# 11_PHY_FE_17-24.net
KiCad netlist of a schematic drawn in Altium Designer
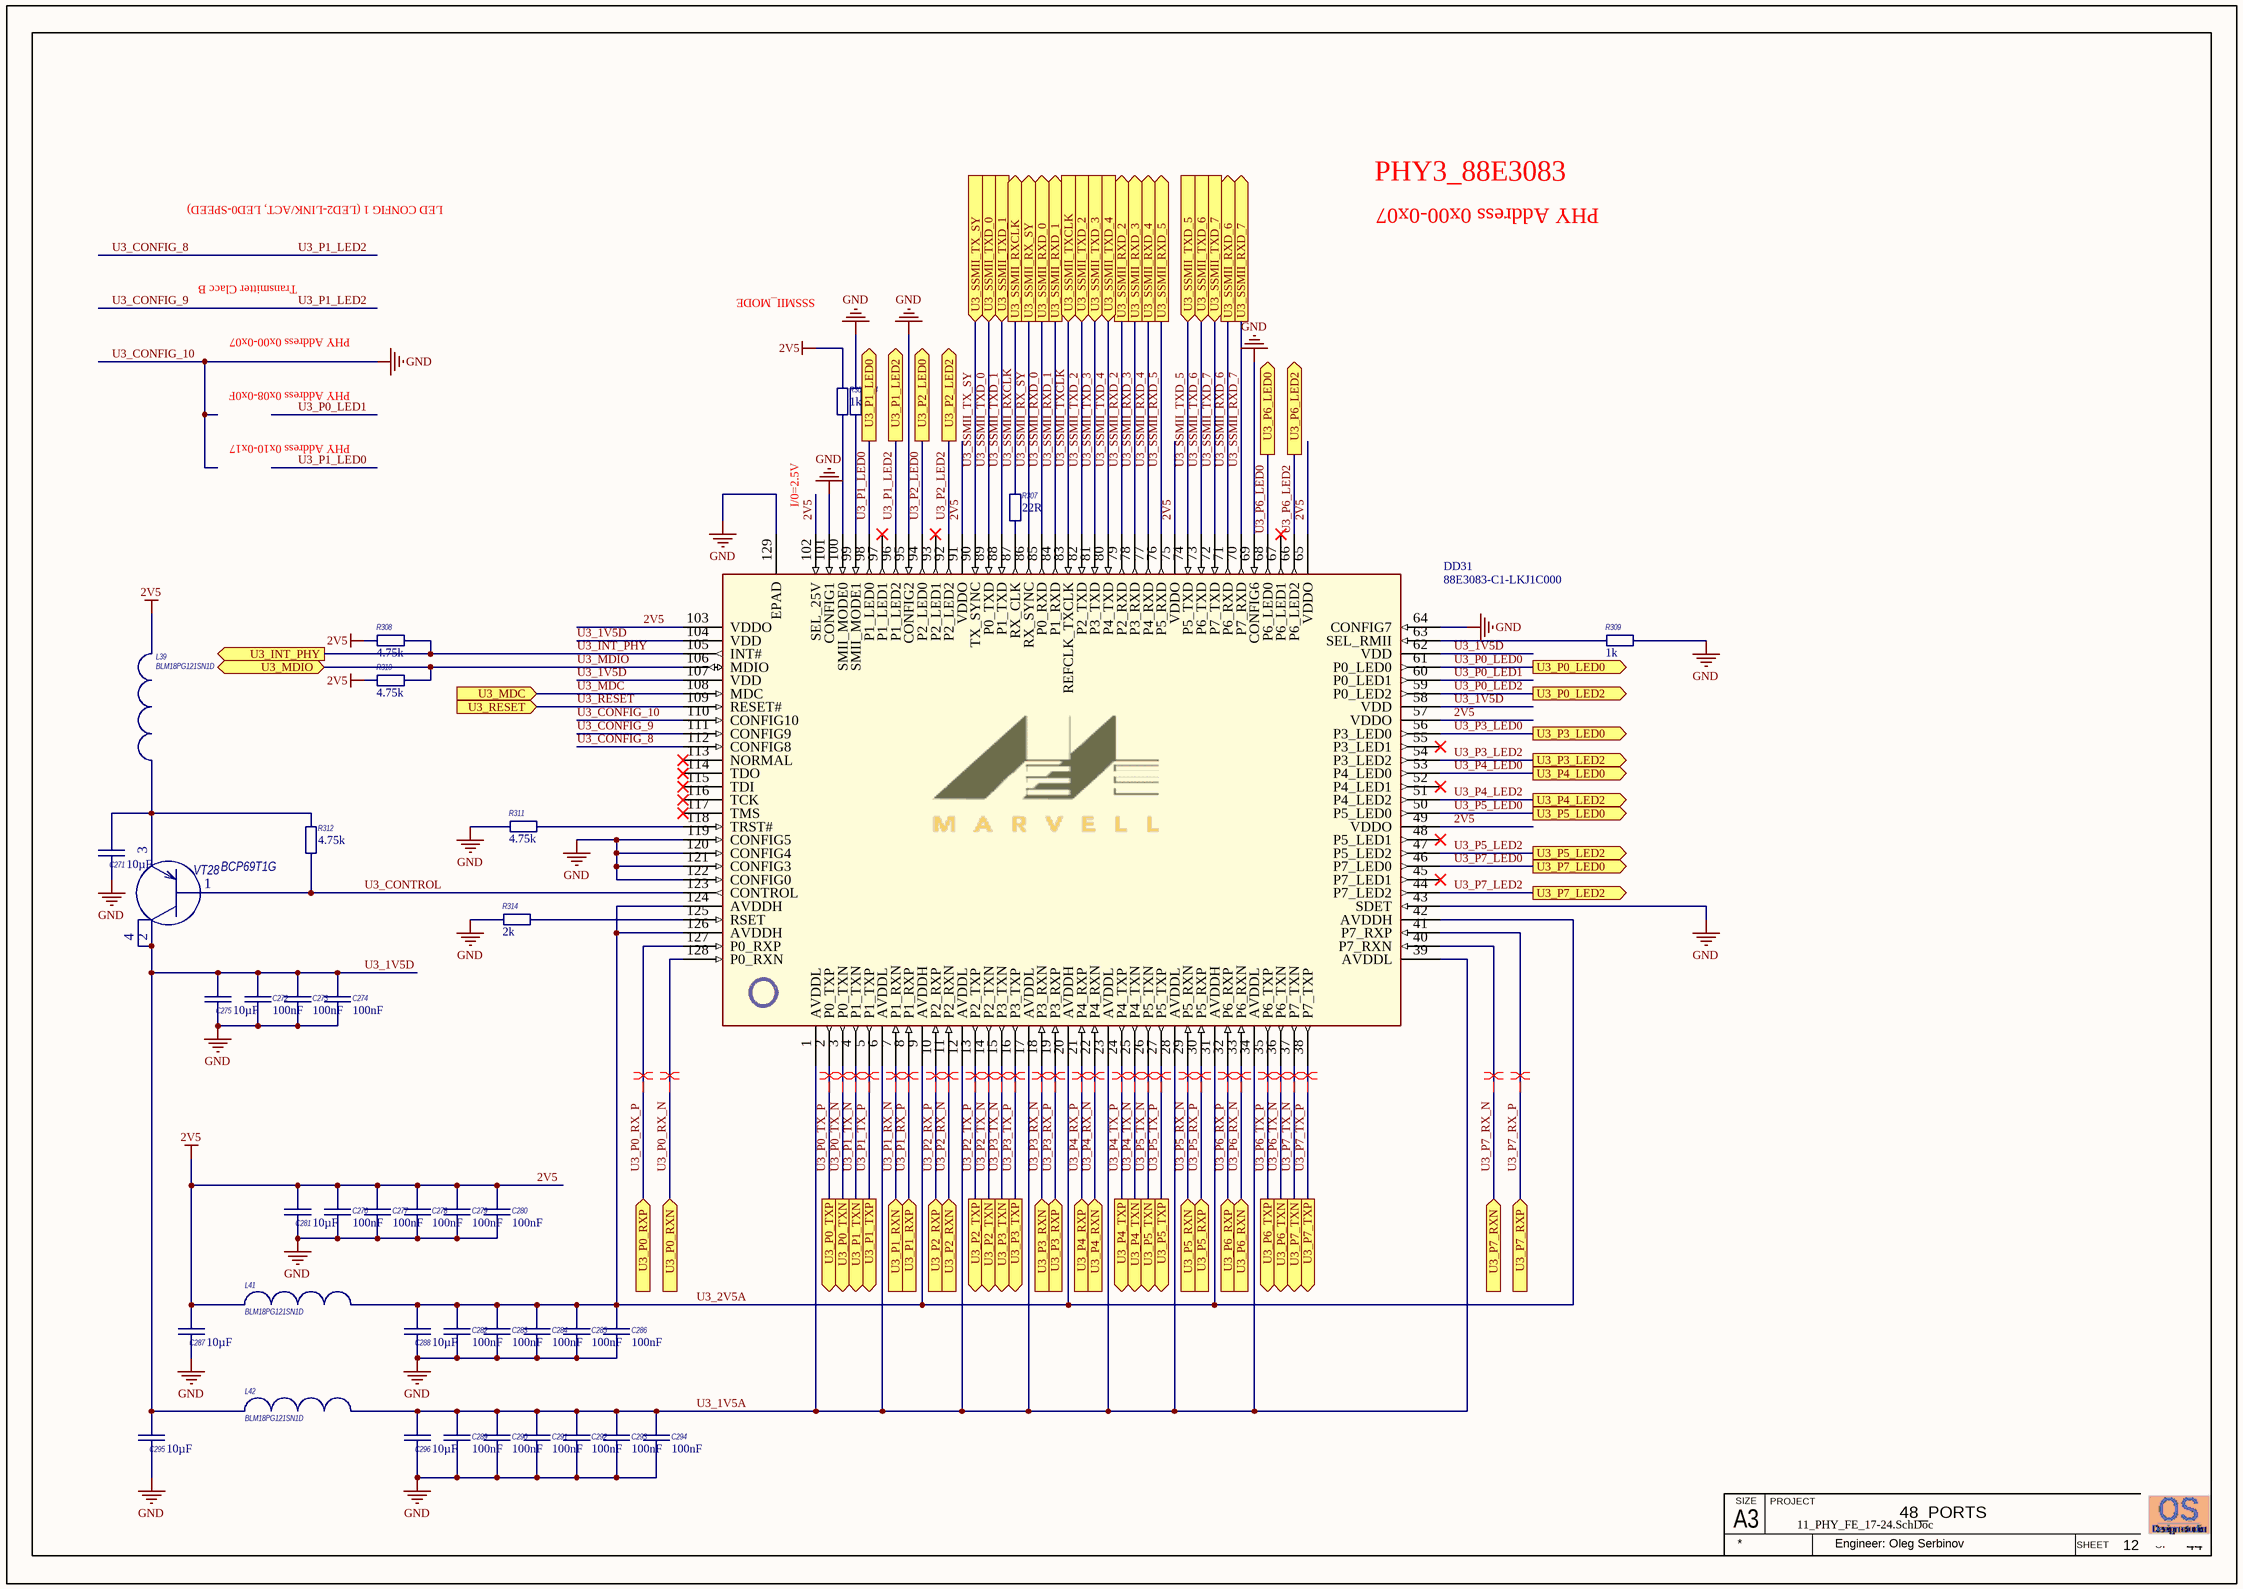
[diagram p0: 11_PHY_FE_17-24.SchDoc]

(export (version "E")
  (design (tool "Eeschema 10.0.6"))
  (components
    (comp (ref "C271")
      (value "GRM21BR61C106KE15")
      (footprint "CAPC2012[0805]")
      (description "C0805, 10uF 10%, 16V, X5R")
      (fields
        (field (name "MANUFACTURER") "Murata")
        (field (name "TOLERANCE") "±10%")
        (field (name "CAPACITANCE") "10µF")
      )
      (libsource (lib "CAPACITORS") (part "GRM21BR61C106KE15"))
    )
    (comp (ref "C272")
      (value "GRM155R71E104KE14D")
      (footprint "C0402_IPC High Density")
      (description "C0402, 100nF, 25V, X7R")
      (fields
        (field (name "MANUFACTURER") "Murata")
        (field (name "CAPACITANCE") "100nF")
        (field (name "CUSTOMER PART NUMBER") "Конденсатор, 100n, 0402, 25V, X7R, 10%")
      )
      (libsource (lib "CAPACITORS") (part "GRM155R71E104KE14D"))
    )
    (comp (ref "C273")
      (value "GRM155R71E104KE14D")
      (footprint "C0402_IPC High Density")
      (description "C0402, 100nF, 25V, X7R")
      (fields
        (field (name "MANUFACTURER") "Murata")
        (field (name "CAPACITANCE") "100nF")
        (field (name "CUSTOMER PART NUMBER") "Конденсатор, 100n, 0402, 25V, X7R, 10%")
      )
      (libsource (lib "CAPACITORS") (part "GRM155R71E104KE14D"))
    )
    (comp (ref "C274")
      (value "GRM155R71E104KE14D")
      (footprint "C0402_IPC High Density")
      (description "C0402, 100nF, 25V, X7R")
      (fields
        (field (name "MANUFACTURER") "Murata")
        (field (name "CAPACITANCE") "100nF")
        (field (name "CUSTOMER PART NUMBER") "Конденсатор, 100n, 0402, 25V, X7R, 10%")
      )
      (libsource (lib "CAPACITORS") (part "GRM155R71E104KE14D"))
    )
    (comp (ref "C275")
      (value "GRM21BR61C106KE15")
      (footprint "CAPC2012[0805]")
      (description "C0805, 10uF 10%, 16V, X5R")
      (fields
        (field (name "MANUFACTURER") "Murata")
        (field (name "TOLERANCE") "±10%")
        (field (name "CAPACITANCE") "10µF")
      )
      (libsource (lib "CAPACITORS") (part "GRM21BR61C106KE15"))
    )
    (comp (ref "C276")
      (value "GRM155R71E104KE14D")
      (footprint "C0402_IPC High Density")
      (description "C0402, 100nF, 25V, X7R")
      (fields
        (field (name "MANUFACTURER") "Murata")
        (field (name "CAPACITANCE") "100nF")
        (field (name "CUSTOMER PART NUMBER") "Конденсатор, 100n, 0402, 25V, X7R, 10%")
      )
      (libsource (lib "CAPACITORS") (part "GRM155R71E104KE14D"))
    )
    (comp (ref "C277")
      (value "GRM155R71E104KE14D")
      (footprint "C0402_IPC High Density")
      (description "C0402, 100nF, 25V, X7R")
      (fields
        (field (name "MANUFACTURER") "Murata")
        (field (name "CAPACITANCE") "100nF")
        (field (name "CUSTOMER PART NUMBER") "Конденсатор, 100n, 0402, 25V, X7R, 10%")
      )
      (libsource (lib "CAPACITORS") (part "GRM155R71E104KE14D"))
    )
    (comp (ref "C278")
      (value "GRM155R71E104KE14D")
      (footprint "C0402_IPC High Density")
      (description "C0402, 100nF, 25V, X7R")
      (fields
        (field (name "MANUFACTURER") "Murata")
        (field (name "CAPACITANCE") "100nF")
        (field (name "CUSTOMER PART NUMBER") "Конденсатор, 100n, 0402, 25V, X7R, 10%")
      )
      (libsource (lib "CAPACITORS") (part "GRM155R71E104KE14D"))
    )
    (comp (ref "C279")
      (value "GRM155R71E104KE14D")
      (footprint "C0402_IPC High Density")
      (description "C0402, 100nF, 25V, X7R")
      (fields
        (field (name "MANUFACTURER") "Murata")
        (field (name "CAPACITANCE") "100nF")
        (field (name "CUSTOMER PART NUMBER") "Конденсатор, 100n, 0402, 25V, X7R, 10%")
      )
      (libsource (lib "CAPACITORS") (part "GRM155R71E104KE14D"))
    )
    (comp (ref "C280")
      (value "GRM155R71E104KE14D")
      (footprint "C0402_IPC High Density")
      (description "C0402, 100nF, 25V, X7R")
      (fields
        (field (name "MANUFACTURER") "Murata")
        (field (name "CAPACITANCE") "100nF")
        (field (name "CUSTOMER PART NUMBER") "Конденсатор, 100n, 0402, 25V, X7R, 10%")
      )
      (libsource (lib "CAPACITORS") (part "GRM155R71E104KE14D"))
    )
    (comp (ref "C281")
      (value "GRM21BR61C106KE15")
      (footprint "CAPC2012[0805]")
      (description "C0805, 10uF 10%, 16V, X5R")
      (fields
        (field (name "MANUFACTURER") "Murata")
        (field (name "TOLERANCE") "±10%")
        (field (name "CAPACITANCE") "10µF")
      )
      (libsource (lib "CAPACITORS") (part "GRM21BR61C106KE15"))
    )
    (comp (ref "C282")
      (value "GRM155R71E104KE14D")
      (footprint "C0402_IPC High Density")
      (description "C0402, 100nF, 25V, X7R")
      (fields
        (field (name "MANUFACTURER") "Murata")
        (field (name "CAPACITANCE") "100nF")
        (field (name "CUSTOMER PART NUMBER") "Конденсатор, 100n, 0402, 25V, X7R, 10%")
      )
      (libsource (lib "CAPACITORS") (part "GRM155R71E104KE14D"))
    )
    (comp (ref "C283")
      (value "GRM155R71E104KE14D")
      (footprint "C0402_IPC High Density")
      (description "C0402, 100nF, 25V, X7R")
      (fields
        (field (name "MANUFACTURER") "Murata")
        (field (name "CAPACITANCE") "100nF")
        (field (name "CUSTOMER PART NUMBER") "Конденсатор, 100n, 0402, 25V, X7R, 10%")
      )
      (libsource (lib "CAPACITORS") (part "GRM155R71E104KE14D"))
    )
    (comp (ref "C284")
      (value "GRM155R71E104KE14D")
      (footprint "C0402_IPC High Density")
      (description "C0402, 100nF, 25V, X7R")
      (fields
        (field (name "MANUFACTURER") "Murata")
        (field (name "CAPACITANCE") "100nF")
        (field (name "CUSTOMER PART NUMBER") "Конденсатор, 100n, 0402, 25V, X7R, 10%")
      )
      (libsource (lib "CAPACITORS") (part "GRM155R71E104KE14D"))
    )
    (comp (ref "C285")
      (value "GRM155R71E104KE14D")
      (footprint "C0402_IPC High Density")
      (description "C0402, 100nF, 25V, X7R")
      (fields
        (field (name "MANUFACTURER") "Murata")
        (field (name "CAPACITANCE") "100nF")
        (field (name "CUSTOMER PART NUMBER") "Конденсатор, 100n, 0402, 25V, X7R, 10%")
      )
      (libsource (lib "CAPACITORS") (part "GRM155R71E104KE14D"))
    )
    (comp (ref "C286")
      (value "GRM155R71E104KE14D")
      (footprint "C0402_IPC High Density")
      (description "C0402, 100nF, 25V, X7R")
      (fields
        (field (name "MANUFACTURER") "Murata")
        (field (name "CAPACITANCE") "100nF")
        (field (name "CUSTOMER PART NUMBER") "Конденсатор, 100n, 0402, 25V, X7R, 10%")
      )
      (libsource (lib "CAPACITORS") (part "GRM155R71E104KE14D"))
    )
    (comp (ref "C287")
      (value "GRM21BR61C106KE15")
      (footprint "CAPC2012[0805]")
      (description "C0805, 10uF 10%, 16V, X5R")
      (fields
        (field (name "MANUFACTURER") "Murata")
        (field (name "TOLERANCE") "±10%")
        (field (name "CAPACITANCE") "10µF")
      )
      (libsource (lib "CAPACITORS") (part "GRM21BR61C106KE15"))
    )
    (comp (ref "C288")
      (value "GRM21BR61C106KE15")
      (footprint "CAPC2012[0805]")
      (description "C0805, 10uF 10%, 16V, X5R")
      (fields
        (field (name "MANUFACTURER") "Murata")
        (field (name "TOLERANCE") "±10%")
        (field (name "CAPACITANCE") "10µF")
      )
      (libsource (lib "CAPACITORS") (part "GRM21BR61C106KE15"))
    )
    (comp (ref "C289")
      (value "GRM155R71E104KE14D")
      (footprint "C0402_IPC High Density")
      (description "C0402, 100nF, 25V, X7R")
      (fields
        (field (name "MANUFACTURER") "Murata")
        (field (name "CAPACITANCE") "100nF")
        (field (name "CUSTOMER PART NUMBER") "Конденсатор, 100n, 0402, 25V, X7R, 10%")
      )
      (libsource (lib "CAPACITORS") (part "GRM155R71E104KE14D"))
    )
    (comp (ref "C290")
      (value "GRM155R71E104KE14D")
      (footprint "C0402_IPC High Density")
      (description "C0402, 100nF, 25V, X7R")
      (fields
        (field (name "MANUFACTURER") "Murata")
        (field (name "CAPACITANCE") "100nF")
        (field (name "CUSTOMER PART NUMBER") "Конденсатор, 100n, 0402, 25V, X7R, 10%")
      )
      (libsource (lib "CAPACITORS") (part "GRM155R71E104KE14D"))
    )
    (comp (ref "C291")
      (value "GRM155R71E104KE14D")
      (footprint "C0402_IPC High Density")
      (description "C0402, 100nF, 25V, X7R")
      (fields
        (field (name "MANUFACTURER") "Murata")
        (field (name "CAPACITANCE") "100nF")
        (field (name "CUSTOMER PART NUMBER") "Конденсатор, 100n, 0402, 25V, X7R, 10%")
      )
      (libsource (lib "CAPACITORS") (part "GRM155R71E104KE14D"))
    )
    (comp (ref "C292")
      (value "GRM155R71E104KE14D")
      (footprint "C0402_IPC High Density")
      (description "C0402, 100nF, 25V, X7R")
      (fields
        (field (name "MANUFACTURER") "Murata")
        (field (name "CAPACITANCE") "100nF")
        (field (name "CUSTOMER PART NUMBER") "Конденсатор, 100n, 0402, 25V, X7R, 10%")
      )
      (libsource (lib "CAPACITORS") (part "GRM155R71E104KE14D"))
    )
    (comp (ref "C293")
      (value "GRM155R71E104KE14D")
      (footprint "C0402_IPC High Density")
      (description "C0402, 100nF, 25V, X7R")
      (fields
        (field (name "MANUFACTURER") "Murata")
        (field (name "CAPACITANCE") "100nF")
        (field (name "CUSTOMER PART NUMBER") "Конденсатор, 100n, 0402, 25V, X7R, 10%")
      )
      (libsource (lib "CAPACITORS") (part "GRM155R71E104KE14D"))
    )
    (comp (ref "C294")
      (value "GRM155R71E104KE14D")
      (footprint "C0402_IPC High Density")
      (description "C0402, 100nF, 25V, X7R")
      (fields
        (field (name "MANUFACTURER") "Murata")
        (field (name "CAPACITANCE") "100nF")
        (field (name "CUSTOMER PART NUMBER") "Конденсатор, 100n, 0402, 25V, X7R, 10%")
      )
      (libsource (lib "CAPACITORS") (part "GRM155R71E104KE14D"))
    )
    (comp (ref "C295")
      (value "GRM21BR61C106KE15")
      (footprint "CAPC2012[0805]")
      (description "C0805, 10uF 10%, 16V, X5R")
      (fields
        (field (name "MANUFACTURER") "Murata")
        (field (name "TOLERANCE") "±10%")
        (field (name "CAPACITANCE") "10µF")
      )
      (libsource (lib "CAPACITORS") (part "GRM21BR61C106KE15"))
    )
    (comp (ref "C296")
      (value "GRM21BR61C106KE15")
      (footprint "CAPC2012[0805]")
      (description "C0805, 10uF 10%, 16V, X5R")
      (fields
        (field (name "MANUFACTURER") "Murata")
        (field (name "TOLERANCE") "±10%")
        (field (name "CAPACITANCE") "10µF")
      )
      (libsource (lib "CAPACITORS") (part "GRM21BR61C106KE15"))
    )
    (comp (ref "DD31")
      (value "88E3083-C1-LKJ1C000")
      (footprint "LQFP-128N")
      (description "IC 10/100BASE-T OCTAL PHY")
      (fields
        (field (name "CUSTOMER PART NUMBER") "Микросхема, 88E3083-C1-LKJ1C000, IC 10/100BASE-T OCTAL PHY, 128 LQFP")
        (field (name "MANUFACTURER") "Marvell Technology Group")
      )
      (libsource (lib "DIGITAL and ANALIG ICs") (part "88E3083-C1-LKJ1C000"))
    )
    (comp (ref "L39")
      (value "BLM18PG121SN1D")
      (footprint "INDC1608X95N")
      (description "FILTER BLM18 (0603, 2A)")
      (fields
        (field (name "MANUFACTURER") "Murata")
        (field (name "RPART NUMBER") "MPZ1608S121ATAH0 ; CIC10P121NC ; MPZ1608S121ATDH5 ; BLM18PG121SH1D ; 742792625")
      )
      (libsource (lib "INDUCTORS") (part "BLM18PG121SN1D"))
    )
    (comp (ref "L41")
      (value "BLM18PG121SN1D")
      (footprint "INDC1608X95N")
      (description "FILTER BLM18 (0603, 2A)")
      (fields
        (field (name "MANUFACTURER") "Murata")
        (field (name "RPART NUMBER") "MPZ1608S121ATAH0 ; CIC10P121NC ; MPZ1608S121ATDH5 ; BLM18PG121SH1D ; 742792625")
      )
      (libsource (lib "INDUCTORS") (part "BLM18PG121SN1D"))
    )
    (comp (ref "L42")
      (value "BLM18PG121SN1D")
      (footprint "INDC1608X95N")
      (description "FILTER BLM18 (0603, 2A)")
      (fields
        (field (name "MANUFACTURER") "Murata")
        (field (name "RPART NUMBER") "MPZ1608S121ATAH0 ; CIC10P121NC ; MPZ1608S121ATDH5 ; BLM18PG121SH1D ; 742792625")
      )
      (libsource (lib "INDUCTORS") (part "BLM18PG121SN1D"))
    )
    (comp (ref "R303")
      (value "ERJ-2RKF1001X")
      (footprint "R0402_IPC High Density")
      (description "R0402, 1k 1%")
      (fields
        (field (name "MANUFACTURER") "Panasonic")
        (field (name "TOLERANCE") "1 %")
        (field (name "RESISTANCE") "1k")
      )
      (libsource (lib "RESISTOR") (part "ERJ-2RKF1001X"))
    )
    (comp (ref "R304")
      (value "ERJ-2RKF1001X")
      (footprint "R0402_IPC High Density")
      (description "R0402, 1k 1%")
      (fields
        (field (name "MANUFACTURER") "Panasonic")
        (field (name "TOLERANCE") "1 %")
        (field (name "RESISTANCE") "1k")
      )
      (libsource (lib "RESISTOR") (part "ERJ-2RKF1001X"))
    )
    (comp (ref "R307")
      (value "ERJ-2RKF22R0X")
      (footprint "R0402_IPC High Density")
      (description "R0402, 22R 1%")
      (fields
        (field (name "MANUFACTURER") "Panasonic")
        (field (name "RESISTANCE") "22R")
        (field (name "CUSTOMER PART NUMBER") "Резистор, 22R, 0402, 1%")
      )
      (libsource (lib "RESISTOR") (part "ERJ-2RKF22R0X"))
    )
    (comp (ref "R308")
      (value "ERJ-2RKF4751X")
      (footprint "R0402_IPC High Density")
      (description "R0402, 4.75k 1%")
      (fields
        (field (name "TOLERANCE") "±1%")
        (field (name "MANUFACTURER") "Panasonic")
        (field (name "RESISTANCE (OHMS)") "4.75k")
      )
      (libsource (lib "RESISTOR") (part "ERJ-2RKF4751X"))
    )
    (comp (ref "R309")
      (value "ERJ-2RKF1001X")
      (footprint "R0402_IPC High Density")
      (description "R0402, 1k 1%")
      (fields
        (field (name "MANUFACTURER") "Panasonic")
        (field (name "TOLERANCE") "1 %")
        (field (name "RESISTANCE") "1k")
      )
      (libsource (lib "RESISTOR") (part "ERJ-2RKF1001X"))
    )
    (comp (ref "R310")
      (value "ERJ-2RKF4751X")
      (footprint "R0402_IPC High Density")
      (description "R0402, 4.75k 1%")
      (fields
        (field (name "TOLERANCE") "±1%")
        (field (name "MANUFACTURER") "Panasonic")
        (field (name "RESISTANCE (OHMS)") "4.75k")
      )
      (libsource (lib "RESISTOR") (part "ERJ-2RKF4751X"))
    )
    (comp (ref "R311")
      (value "ERJ-2RKF4751X")
      (footprint "R0402_IPC High Density")
      (description "R0402, 4.75k 1%")
      (fields
        (field (name "TOLERANCE") "±1%")
        (field (name "MANUFACTURER") "Panasonic")
        (field (name "RESISTANCE (OHMS)") "4.75k")
      )
      (libsource (lib "RESISTOR") (part "ERJ-2RKF4751X"))
    )
    (comp (ref "R312")
      (value "ERJ-2RKF4751X")
      (footprint "R0402_IPC High Density")
      (description "R0402, 4.75k 1%")
      (fields
        (field (name "TOLERANCE") "±1%")
        (field (name "MANUFACTURER") "Panasonic")
        (field (name "RESISTANCE (OHMS)") "4.75k")
      )
      (libsource (lib "RESISTOR") (part "ERJ-2RKF4751X"))
    )
    (comp (ref "R314")
      (value "ERJ-2RKF2001X")
      (footprint "R0402_IPC High Density")
      (description "R0402, 2k 1%")
      (fields
        (field (name "TOLERANCE") "±1%")
        (field (name "MANUFACTURER") "Panasonic")
        (field (name "RESISTANCE (OHMS)") "2k")
      )
      (libsource (lib "RESISTOR") (part "ERJ-2RKF2001X"))
    )
    (comp (ref "VT28")
      (value "BCP69T1G")
      (footprint "SOT223_N")
      (description "TRANSISTOR PNP -20V -1A SOT-223")
      (fields
        (field (name "MANUFACTURER") "ON Semiconductor")
        (field (name "MANUFACTURER PART NUMBER") "BCP69T1")
      )
      (libsource (lib "TRANSISTORS") (part "BCP69T1"))
    )
  )
  (nets
    (net (code "1") (name "/U3_1V5A") (class "Default")
      (node (ref "C289") (pin "2") (pintype "passive"))
      (node (ref "C290") (pin "2") (pintype "passive"))
      (node (ref "C291") (pin "2") (pintype "passive"))
      (node (ref "C292") (pin "2") (pintype "passive"))
      (node (ref "C293") (pin "2") (pintype "passive"))
      (node (ref "C294") (pin "2") (pintype "passive"))
      (node (ref "C296") (pin "2") (pintype "passive"))
      (node (ref "DD31") (pin "1") (pinfunction "AVDDL_1") (pintype "power_in"))
      (node (ref "DD31") (pin "12") (pinfunction "AVDDL_12") (pintype "power_in"))
      (node (ref "DD31") (pin "17") (pinfunction "AVDDL_17") (pintype "power_in"))
      (node (ref "DD31") (pin "23") (pinfunction "AVDDL_23") (pintype "power_in"))
      (node (ref "DD31") (pin "28") (pinfunction "AVDDL_28") (pintype "power_in"))
      (node (ref "DD31") (pin "34") (pinfunction "AVDDL_34") (pintype "power_in"))
      (node (ref "DD31") (pin "39") (pinfunction "AVDDL_39") (pintype "power_in"))
      (node (ref "DD31") (pin "6") (pinfunction "AVDDL_6") (pintype "power_in"))
      (node (ref "L42") (pin "2") (pinfunction "2_2") (pintype "passive"))
    )
    (net (code "2") (name "/U3_1V5D") (class "Default")
      (node (ref "C272") (pin "2") (pintype "passive"))
      (node (ref "C273") (pin "2") (pintype "passive"))
      (node (ref "C274") (pin "2") (pintype "passive"))
      (node (ref "C275") (pin "2") (pintype "passive"))
      (node (ref "C295") (pin "2") (pintype "passive"))
      (node (ref "DD31") (pin "104") (pinfunction "VDD_104") (pintype "power_in"))
      (node (ref "DD31") (pin "107") (pinfunction "VDD_107") (pintype "power_in"))
      (node (ref "DD31") (pin "58") (pinfunction "VDD_58") (pintype "power_in"))
      (node (ref "DD31") (pin "62") (pinfunction "VDD_62") (pintype "power_in"))
      (node (ref "L42") (pin "1") (pinfunction "1_1") (pintype "passive"))
      (node (ref "VT28") (pin "2") (pinfunction "K_2") (pintype "passive"))
      (node (ref "VT28") (pin "4") (pinfunction "K_4") (pintype "passive"))
    )
    (net (code "3") (name "/U3_2V5A") (class "Default")
      (node (ref "C282") (pin "2") (pintype "passive"))
      (node (ref "C283") (pin "2") (pintype "passive"))
      (node (ref "C284") (pin "2") (pintype "passive"))
      (node (ref "C285") (pin "2") (pintype "passive"))
      (node (ref "C286") (pin "2") (pintype "passive"))
      (node (ref "C288") (pin "2") (pintype "passive"))
      (node (ref "DD31") (pin "124") (pinfunction "AVDDH_124") (pintype "power_in"))
      (node (ref "DD31") (pin "126") (pinfunction "AVDDH_126") (pintype "power_in"))
      (node (ref "DD31") (pin "20") (pinfunction "AVDDH_20") (pintype "power_in"))
      (node (ref "DD31") (pin "31") (pinfunction "AVDDH_31") (pintype "power_in"))
      (node (ref "DD31") (pin "42") (pinfunction "AVDDH_42") (pintype "power_in"))
      (node (ref "DD31") (pin "9") (pinfunction "AVDDH_9") (pintype "power_in"))
      (node (ref "L41") (pin "2") (pinfunction "2_2") (pintype "passive"))
    )
    (net (code "4") (name "/U3_CONFIG_8") (class "Default")
      (node (ref "DD31") (pin "111") (pinfunction "CONFIG9_111") (pintype "input"))
      (node (ref "DD31") (pin "112") (pinfunction "CONFIG8_112") (pintype "input"))
      (node (ref "DD31") (pin "96") (pinfunction "P1_LED2_96") (pintype "output"))
    )
    (net (code "5") (name "/U3_CONTROL") (class "Default")
      (node (ref "DD31") (pin "123") (pinfunction "CONTROL_123") (pintype "output"))
      (node (ref "R312") (pin "1") (pintype "passive"))
      (node (ref "VT28") (pin "1") (pinfunction "B_1") (pintype "passive"))
    )
    (net (code "6") (name "/U3_INT_PHY") (class "Default")
      (node (ref "DD31") (pin "105") (pinfunction "INT#_105") (pintype "output"))
      (node (ref "R308") (pin "2") (pintype "passive"))
    )
    (net (code "7") (name "/U3_MDC") (class "Default")
      (node (ref "DD31") (pin "108") (pinfunction "MDC_108") (pintype "input"))
    )
    (net (code "8") (name "/U3_MDIO") (class "Default")
      (node (ref "DD31") (pin "106") (pinfunction "MDIO_106") (pintype "bidirectional"))
      (node (ref "R310") (pin "2") (pintype "passive"))
    )
    (net (code "9") (name "/U3_P0_LED0") (class "Default")
      (node (ref "DD31") (pin "61") (pinfunction "P0_LED0_61") (pintype "output"))
    )
    (net (code "10") (name "/U3_P0_LED1") (class "Default")
      (node (ref "DD31") (pin "60") (pinfunction "P0_LED1_60") (pintype "output"))
    )
    (net (code "11") (name "/U3_P0_LED2") (class "Default")
      (node (ref "DD31") (pin "59") (pinfunction "P0_LED2_59") (pintype "output"))
    )
    (net (code "12") (name "/U3_P0_RX_N") (class "Default")
      (node (ref "DD31") (pin "128") (pinfunction "P0_RXN_128") (pintype "input"))
    )
    (net (code "13") (name "/U3_P0_RX_P") (class "Default")
      (node (ref "DD31") (pin "127") (pinfunction "P0_RXP_127") (pintype "input"))
    )
    (net (code "14") (name "/U3_P0_TX_N") (class "Default")
      (node (ref "DD31") (pin "3") (pinfunction "P0_TXN_3") (pintype "output"))
    )
    (net (code "15") (name "/U3_P0_TX_P") (class "Default")
      (node (ref "DD31") (pin "2") (pinfunction "P0_TXP_2") (pintype "output"))
    )
    (net (code "16") (name "/U3_P1_LED0") (class "Default")
      (node (ref "DD31") (pin "98") (pinfunction "P1_LED0_98") (pintype "output"))
    )
    (net (code "17") (name "/U3_P1_RX_N") (class "Default")
      (node (ref "DD31") (pin "7") (pinfunction "P1_RXN_7") (pintype "input"))
    )
    (net (code "18") (name "/U3_P1_RX_P") (class "Default")
      (node (ref "DD31") (pin "8") (pinfunction "P1_RXP_8") (pintype "input"))
    )
    (net (code "19") (name "/U3_P1_TX_N") (class "Default")
      (node (ref "DD31") (pin "4") (pinfunction "P1_TXN_4") (pintype "output"))
    )
    (net (code "20") (name "/U3_P1_TX_P") (class "Default")
      (node (ref "DD31") (pin "5") (pinfunction "P1_TXP_5") (pintype "output"))
    )
    (net (code "21") (name "/U3_P2_LED0") (class "Default")
      (node (ref "DD31") (pin "94") (pinfunction "P2_LED0_94") (pintype "output"))
    )
    (net (code "22") (name "/U3_P2_LED2") (class "Default")
      (node (ref "DD31") (pin "92") (pinfunction "P2_LED2_92") (pintype "output"))
    )
    (net (code "23") (name "/U3_P2_RX_N") (class "Default")
      (node (ref "DD31") (pin "11") (pinfunction "P2_RXN_11") (pintype "input"))
    )
    (net (code "24") (name "/U3_P2_RX_P") (class "Default")
      (node (ref "DD31") (pin "10") (pinfunction "P2_RXP_10") (pintype "input"))
    )
    (net (code "25") (name "/U3_P2_TX_N") (class "Default")
      (node (ref "DD31") (pin "14") (pinfunction "P2_TXN_14") (pintype "output"))
    )
    (net (code "26") (name "/U3_P2_TX_P") (class "Default")
      (node (ref "DD31") (pin "13") (pinfunction "P2_TXP_13") (pintype "output"))
    )
    (net (code "27") (name "/U3_P3_LED0") (class "Default")
      (node (ref "DD31") (pin "56") (pinfunction "P3_LED0_56") (pintype "output"))
    )
    (net (code "28") (name "/U3_P3_LED2") (class "Default")
      (node (ref "DD31") (pin "54") (pinfunction "P3_LED2_54") (pintype "output"))
    )
    (net (code "29") (name "/U3_P3_RX_N") (class "Default")
      (node (ref "DD31") (pin "18") (pinfunction "P3_RXN_18") (pintype "input"))
    )
    (net (code "30") (name "/U3_P3_RX_P") (class "Default")
      (node (ref "DD31") (pin "19") (pinfunction "P3_RXP_19") (pintype "input"))
    )
    (net (code "31") (name "/U3_P3_TX_N") (class "Default")
      (node (ref "DD31") (pin "15") (pinfunction "P3_TXN_15") (pintype "output"))
    )
    (net (code "32") (name "/U3_P3_TX_P") (class "Default")
      (node (ref "DD31") (pin "16") (pinfunction "P3_TXP_16") (pintype "output"))
    )
    (net (code "33") (name "/U3_P4_LED0") (class "Default")
      (node (ref "DD31") (pin "53") (pinfunction "P4_LED0_53") (pintype "output"))
    )
    (net (code "34") (name "/U3_P4_LED2") (class "Default")
      (node (ref "DD31") (pin "51") (pinfunction "P4_LED2_51") (pintype "output"))
    )
    (net (code "35") (name "/U3_P4_RX_N") (class "Default")
      (node (ref "DD31") (pin "22") (pinfunction "P4_RXN_22") (pintype "input"))
    )
    (net (code "36") (name "/U3_P4_RX_P") (class "Default")
      (node (ref "DD31") (pin "21") (pinfunction "P4_RXP_21") (pintype "input"))
    )
    (net (code "37") (name "/U3_P4_TX_N") (class "Default")
      (node (ref "DD31") (pin "25") (pinfunction "P4_TXN_25") (pintype "output"))
    )
    (net (code "38") (name "/U3_P4_TX_P") (class "Default")
      (node (ref "DD31") (pin "24") (pinfunction "P4_TXP_24") (pintype "output"))
    )
    (net (code "39") (name "/U3_P5_LED0") (class "Default")
      (node (ref "DD31") (pin "50") (pinfunction "P5_LED0_50") (pintype "output"))
    )
    (net (code "40") (name "/U3_P5_LED2") (class "Default")
      (node (ref "DD31") (pin "47") (pinfunction "P5_LED2_47") (pintype "output"))
    )
    (net (code "41") (name "/U3_P5_RX_N") (class "Default")
      (node (ref "DD31") (pin "29") (pinfunction "P5_RXN_29") (pintype "input"))
    )
    (net (code "42") (name "/U3_P5_RX_P") (class "Default")
      (node (ref "DD31") (pin "30") (pinfunction "P5_RXP_30") (pintype "input"))
    )
    (net (code "43") (name "/U3_P5_TX_N") (class "Default")
      (node (ref "DD31") (pin "26") (pinfunction "P5_TXN_26") (pintype "output"))
    )
    (net (code "44") (name "/U3_P5_TX_P") (class "Default")
      (node (ref "DD31") (pin "27") (pinfunction "P5_TXP_27") (pintype "output"))
    )
    (net (code "45") (name "/U3_P6_LED0") (class "Default")
      (node (ref "DD31") (pin "68") (pinfunction "P6_LED0_68") (pintype "output"))
    )
    (net (code "46") (name "/U3_P6_LED2") (class "Default")
      (node (ref "DD31") (pin "66") (pinfunction "P6_LED2_66") (pintype "output"))
    )
    (net (code "47") (name "/U3_P6_RX_N") (class "Default")
      (node (ref "DD31") (pin "33") (pinfunction "P6_RXN_33") (pintype "input"))
    )
    (net (code "48") (name "/U3_P6_RX_P") (class "Default")
      (node (ref "DD31") (pin "32") (pinfunction "P6_RXP_32") (pintype "input"))
    )
    (net (code "49") (name "/U3_P6_TX_N") (class "Default")
      (node (ref "DD31") (pin "36") (pinfunction "P6_TXN_36") (pintype "output"))
    )
    (net (code "50") (name "/U3_P6_TX_P") (class "Default")
      (node (ref "DD31") (pin "35") (pinfunction "P6_TXP_35") (pintype "output"))
    )
    (net (code "51") (name "/U3_P7_LED0") (class "Default")
      (node (ref "DD31") (pin "46") (pinfunction "P7_LED0_46") (pintype "output"))
    )
    (net (code "52") (name "/U3_P7_LED2") (class "Default")
      (node (ref "DD31") (pin "44") (pinfunction "P7_LED2_44") (pintype "output"))
    )
    (net (code "53") (name "/U3_P7_RX_N") (class "Default")
      (node (ref "DD31") (pin "40") (pinfunction "P7_RXN_40") (pintype "input"))
    )
    (net (code "54") (name "/U3_P7_RX_P") (class "Default")
      (node (ref "DD31") (pin "41") (pinfunction "P7_RXP_41") (pintype "input"))
    )
    (net (code "55") (name "/U3_P7_TX_N") (class "Default")
      (node (ref "DD31") (pin "37") (pinfunction "P7_TXN_37") (pintype "output"))
    )
    (net (code "56") (name "/U3_P7_TX_P") (class "Default")
      (node (ref "DD31") (pin "38") (pinfunction "P7_TXP_38") (pintype "output"))
    )
    (net (code "57") (name "/U3_RESET") (class "Default")
      (node (ref "DD31") (pin "109") (pinfunction "RESET#_109") (pintype "input"))
    )
    (net (code "58") (name "/U3_SSMII_RXCLK") (class "Default")
      (node (ref "R307") (pin "2") (pintype "passive"))
    )
    (net (code "59") (name "/U3_SSMII_RXD_0") (class "Default")
      (node (ref "DD31") (pin "85") (pinfunction "P0_RXD_85") (pintype "output"))
    )
    (net (code "60") (name "/U3_SSMII_RXD_1") (class "Default")
      (node (ref "DD31") (pin "84") (pinfunction "P1_RXD_84") (pintype "output"))
    )
    (net (code "61") (name "/U3_SSMII_RXD_2") (class "Default")
      (node (ref "DD31") (pin "79") (pinfunction "P2_RXD_79") (pintype "output"))
    )
    (net (code "62") (name "/U3_SSMII_RXD_3") (class "Default")
      (node (ref "DD31") (pin "78") (pinfunction "P3_RXD_78") (pintype "output"))
    )
    (net (code "63") (name "/U3_SSMII_RXD_4") (class "Default")
      (node (ref "DD31") (pin "77") (pinfunction "P4_RXD_77") (pintype "output"))
    )
    (net (code "64") (name "/U3_SSMII_RXD_5") (class "Default")
      (node (ref "DD31") (pin "76") (pinfunction "P5_RXD_76") (pintype "output"))
    )
    (net (code "65") (name "/U3_SSMII_RXD_6") (class "Default")
      (node (ref "DD31") (pin "71") (pinfunction "P6_RXD_71") (pintype "output"))
    )
    (net (code "66") (name "/U3_SSMII_RXD_7") (class "Default")
      (node (ref "DD31") (pin "70") (pinfunction "P7_RXD_70") (pintype "output"))
    )
    (net (code "67") (name "/U3_SSMII_RX_SY") (class "Default")
      (node (ref "DD31") (pin "86") (pinfunction "RX_SYNC_86") (pintype "output"))
    )
    (net (code "68") (name "/U3_SSMII_TXCLK") (class "Default")
      (node (ref "DD31") (pin "83") (pinfunction "REFCLK_TXCLK_83") (pintype "input"))
    )
    (net (code "69") (name "/U3_SSMII_TXD_0") (class "Default")
      (node (ref "DD31") (pin "89") (pinfunction "P0_TXD_89") (pintype "input"))
    )
    (net (code "70") (name "/U3_SSMII_TXD_1") (class "Default")
      (node (ref "DD31") (pin "88") (pinfunction "P1_TXD_88") (pintype "input"))
    )
    (net (code "71") (name "/U3_SSMII_TXD_2") (class "Default")
      (node (ref "DD31") (pin "82") (pinfunction "P2_TXD_82") (pintype "input"))
    )
    (net (code "72") (name "/U3_SSMII_TXD_3") (class "Default")
      (node (ref "DD31") (pin "81") (pinfunction "P3_TXD_81") (pintype "input"))
    )
    (net (code "73") (name "/U3_SSMII_TXD_4") (class "Default")
      (node (ref "DD31") (pin "80") (pinfunction "P4_TXD_80") (pintype "input"))
    )
    (net (code "74") (name "/U3_SSMII_TXD_5") (class "Default")
      (node (ref "DD31") (pin "74") (pinfunction "P5_TXD_74") (pintype "input"))
    )
    (net (code "75") (name "/U3_SSMII_TXD_6") (class "Default")
      (node (ref "DD31") (pin "73") (pinfunction "P6_TXD_73") (pintype "input"))
    )
    (net (code "76") (name "/U3_SSMII_TXD_7") (class "Default")
      (node (ref "DD31") (pin "72") (pinfunction "P7_TXD_72") (pintype "input"))
    )
    (net (code "77") (name "/U3_SSMII_TX_SY") (class "Default")
      (node (ref "DD31") (pin "90") (pinfunction "TX_SYNC_90") (pintype "input"))
    )
    (net (code "78") (name "2V5") (class "Default")
      (node (ref "C276") (pin "2") (pintype "passive"))
      (node (ref "C277") (pin "2") (pintype "passive"))
      (node (ref "C278") (pin "2") (pintype "passive"))
      (node (ref "C279") (pin "2") (pintype "passive"))
      (node (ref "C280") (pin "2") (pintype "passive"))
      (node (ref "C281") (pin "2") (pintype "passive"))
      (node (ref "C287") (pin "2") (pintype "passive"))
      (node (ref "DD31") (pin "102") (pinfunction "SEL_25V_102") (pintype "input"))
      (node (ref "DD31") (pin "103") (pinfunction "VDDO_103") (pintype "power_in"))
      (node (ref "DD31") (pin "49") (pinfunction "VDDO_49") (pintype "power_in"))
      (node (ref "DD31") (pin "57") (pinfunction "VDDO_57") (pintype "power_in"))
      (node (ref "DD31") (pin "65") (pinfunction "VDDO_65") (pintype "power_in"))
      (node (ref "DD31") (pin "75") (pinfunction "VDDO_75") (pintype "power_in"))
      (node (ref "DD31") (pin "91") (pinfunction "VDDO_91") (pintype "power_in"))
      (node (ref "L39") (pin "2") (pinfunction "2_2") (pintype "passive"))
      (node (ref "L41") (pin "1") (pinfunction "1_1") (pintype "passive"))
      (node (ref "R303") (pin "2") (pintype "passive"))
      (node (ref "R308") (pin "1") (pintype "passive"))
      (node (ref "R310") (pin "1") (pintype "passive"))
    )
    (net (code "79") (name "GND") (class "Default")
      (node (ref "C271") (pin "1") (pintype "passive"))
      (node (ref "C272") (pin "1") (pintype "passive"))
      (node (ref "C273") (pin "1") (pintype "passive"))
      (node (ref "C274") (pin "1") (pintype "passive"))
      (node (ref "C275") (pin "1") (pintype "passive"))
      (node (ref "C276") (pin "1") (pintype "passive"))
      (node (ref "C277") (pin "1") (pintype "passive"))
      (node (ref "C278") (pin "1") (pintype "passive"))
      (node (ref "C279") (pin "1") (pintype "passive"))
      (node (ref "C280") (pin "1") (pintype "passive"))
      (node (ref "C281") (pin "1") (pintype "passive"))
      (node (ref "C282") (pin "1") (pintype "passive"))
      (node (ref "C283") (pin "1") (pintype "passive"))
      (node (ref "C284") (pin "1") (pintype "passive"))
      (node (ref "C285") (pin "1") (pintype "passive"))
      (node (ref "C286") (pin "1") (pintype "passive"))
      (node (ref "C287") (pin "1") (pintype "passive"))
      (node (ref "C288") (pin "1") (pintype "passive"))
      (node (ref "C289") (pin "1") (pintype "passive"))
      (node (ref "C290") (pin "1") (pintype "passive"))
      (node (ref "C291") (pin "1") (pintype "passive"))
      (node (ref "C292") (pin "1") (pintype "passive"))
      (node (ref "C293") (pin "1") (pintype "passive"))
      (node (ref "C294") (pin "1") (pintype "passive"))
      (node (ref "C295") (pin "1") (pintype "passive"))
      (node (ref "C296") (pin "1") (pintype "passive"))
      (node (ref "DD31") (pin "101") (pinfunction "CONFIG1_101") (pintype "input"))
      (node (ref "DD31") (pin "110") (pinfunction "CONFIG10_110") (pintype "input"))
      (node (ref "DD31") (pin "119") (pinfunction "CONFIG5_119") (pintype "input"))
      (node (ref "DD31") (pin "120") (pinfunction "CONFIG4_120") (pintype "input"))
      (node (ref "DD31") (pin "121") (pinfunction "CONFIG3_121") (pintype "input"))
      (node (ref "DD31") (pin "122") (pinfunction "CONFIG0_122") (pintype "input"))
      (node (ref "DD31") (pin "129") (pinfunction "EPAD_129") (pintype "power_in"))
      (node (ref "DD31") (pin "43") (pinfunction "SDET_43") (pintype "input"))
      (node (ref "DD31") (pin "64") (pinfunction "CONFIG7_64") (pintype "input"))
      (node (ref "DD31") (pin "69") (pinfunction "CONFIG6_69") (pintype "input"))
      (node (ref "DD31") (pin "95") (pinfunction "CONFIG2_95") (pintype "input"))
      (node (ref "R304") (pin "2") (pintype "passive"))
      (node (ref "R309") (pin "1") (pintype "passive"))
      (node (ref "R311") (pin "1") (pintype "passive"))
      (node (ref "R314") (pin "1") (pintype "passive"))
    )
    (net (code "80") (name "Net-(DD31-RSET)") (class "Default")
      (node (ref "DD31") (pin "125") (pinfunction "RSET_125") (pintype "input"))
      (node (ref "R314") (pin "2") (pintype "passive"))
    )
    (net (code "81") (name "Net-(DD31-RX_CLK)") (class "Default")
      (node (ref "DD31") (pin "87") (pinfunction "RX_CLK_87") (pintype "output"))
      (node (ref "R307") (pin "1") (pintype "passive"))
    )
    (net (code "82") (name "Net-(DD31-SEL_RMII)") (class "Default")
      (node (ref "DD31") (pin "63") (pinfunction "SEL_RMII_63") (pintype "input"))
      (node (ref "R309") (pin "2") (pintype "passive"))
    )
    (net (code "83") (name "Net-(DD31-SMII_MODE0)") (class "Default")
      (node (ref "DD31") (pin "100") (pinfunction "SMII_MODE0_100") (pintype "input"))
      (node (ref "R303") (pin "1") (pintype "passive"))
    )
    (net (code "84") (name "Net-(DD31-SMII_MODE1)") (class "Default")
      (node (ref "DD31") (pin "99") (pinfunction "SMII_MODE1_99") (pintype "input"))
      (node (ref "R304") (pin "1") (pintype "passive"))
    )
    (net (code "85") (name "Net-(DD31-TRST#)") (class "Default")
      (node (ref "DD31") (pin "118") (pinfunction "TRST#_118") (pintype "input"))
      (node (ref "R311") (pin "2") (pintype "passive"))
    )
    (net (code "86") (name "Net-(VT28-E)") (class "Default")
      (node (ref "C271") (pin "2") (pintype "passive"))
      (node (ref "L39") (pin "1") (pinfunction "1_1") (pintype "passive"))
      (node (ref "R312") (pin "2") (pintype "passive"))
      (node (ref "VT28") (pin "3") (pinfunction "E_3") (pintype "passive"))
    )
    (net (code "87") (name "unconnected-(DD31-NORMAL-Pad113)") (class "Default")
      (node (ref "DD31") (pin "113") (pinfunction "NORMAL_113") (pintype "passive+no_connect"))
    )
    (net (code "88") (name "unconnected-(DD31-P1_LED1-Pad97)") (class "Default")
      (node (ref "DD31") (pin "97") (pinfunction "P1_LED1_97") (pintype "output+no_connect"))
    )
    (net (code "89") (name "unconnected-(DD31-P2_LED1-Pad93)") (class "Default")
      (node (ref "DD31") (pin "93") (pinfunction "P2_LED1_93") (pintype "output+no_connect"))
    )
    (net (code "90") (name "unconnected-(DD31-P3_LED1-Pad55)") (class "Default")
      (node (ref "DD31") (pin "55") (pinfunction "P3_LED1_55") (pintype "output+no_connect"))
    )
    (net (code "91") (name "unconnected-(DD31-P4_LED1-Pad52)") (class "Default")
      (node (ref "DD31") (pin "52") (pinfunction "P4_LED1_52") (pintype "output+no_connect"))
    )
    (net (code "92") (name "unconnected-(DD31-P5_LED1-Pad48)") (class "Default")
      (node (ref "DD31") (pin "48") (pinfunction "P5_LED1_48") (pintype "output+no_connect"))
    )
    (net (code "93") (name "unconnected-(DD31-P6_LED1-Pad67)") (class "Default")
      (node (ref "DD31") (pin "67") (pinfunction "P6_LED1_67") (pintype "output+no_connect"))
    )
    (net (code "94") (name "unconnected-(DD31-P7_LED1-Pad45)") (class "Default")
      (node (ref "DD31") (pin "45") (pinfunction "P7_LED1_45") (pintype "output+no_connect"))
    )
    (net (code "95") (name "unconnected-(DD31-TCK-Pad116)") (class "Default")
      (node (ref "DD31") (pin "116") (pinfunction "TCK_116") (pintype "passive+no_connect"))
    )
    (net (code "96") (name "unconnected-(DD31-TDI-Pad115)") (class "Default")
      (node (ref "DD31") (pin "115") (pinfunction "TDI_115") (pintype "passive+no_connect"))
    )
    (net (code "97") (name "unconnected-(DD31-TDO-Pad114)") (class "Default")
      (node (ref "DD31") (pin "114") (pinfunction "TDO_114") (pintype "passive+no_connect"))
    )
    (net (code "98") (name "unconnected-(DD31-TMS-Pad117)") (class "Default")
      (node (ref "DD31") (pin "117") (pinfunction "TMS_117") (pintype "passive+no_connect"))
    )
  )
)
